# SensorCheck.net
KiCad netlist of a schematic drawn in Altium Designer
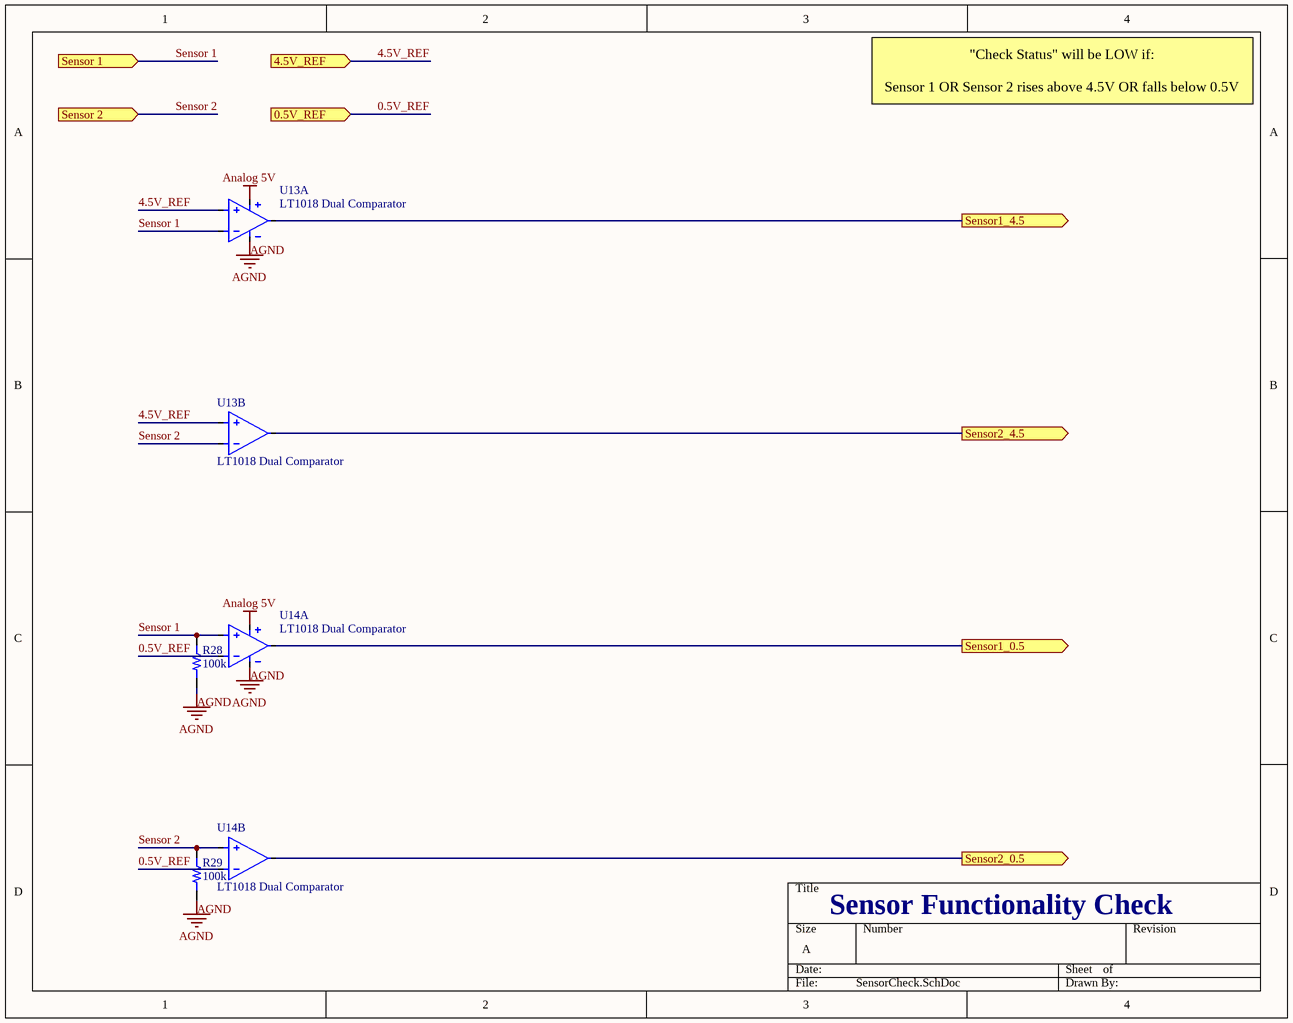
[diagram p0: SensorCheck.SchDoc]

(export (version "E")
  (design (tool "Eeschema 10.0.6"))
  (components
    (comp (ref "R28")
      (value "resistor")
      (footprint "0603")
      (fields (field (name "RESISTANCE") "100k"))
      (libsource (lib "altlib") (part "resistor"))
    )
    (comp (ref "R29")
      (value "resistor")
      (footprint "0603")
      (fields (field (name "RESISTANCE") "100k"))
      (libsource (lib "altlib") (part "resistor"))
    )
    (comp (ref "U13")
      (value "LT1018 Dual Comparator")
      (footprint "SOIC-8")
      (libsource (lib "altlib") (part "LT1018 Dual Comparator"))
    )
    (comp (ref "U14")
      (value "LT1018 Dual Comparator")
      (footprint "SOIC-8")
      (libsource (lib "altlib") (part "LT1018 Dual Comparator"))
    )
  )
  (nets
    (net (code "1") (name "/0.5V_REF") (class "Default")
      (node (ref "U14") (pin "4") (pinfunction "-IN_B_4") (pintype "passive"))
      (node (ref "U14") (pin "8") (pinfunction "-IN_A_8") (pintype "passive"))
    )
    (net (code "2") (name "/4.5V_REF") (class "Default")
      (node (ref "U13") (pin "1") (pinfunction "+IN_A_1") (pintype "passive"))
      (node (ref "U13") (pin "3") (pinfunction "+IN_B_3") (pintype "passive"))
    )
    (net (code "3") (name "/Sensor 1") (class "Default")
      (node (ref "R28") (pin "2") (pinfunction "2_2") (pintype "passive"))
      (node (ref "U13") (pin "8") (pinfunction "-IN_A_8") (pintype "passive"))
      (node (ref "U14") (pin "1") (pinfunction "+IN_A_1") (pintype "passive"))
    )
    (net (code "4") (name "/Sensor 2") (class "Default")
      (node (ref "R29") (pin "2") (pinfunction "2_2") (pintype "passive"))
      (node (ref "U13") (pin "4") (pinfunction "-IN_B_4") (pintype "passive"))
      (node (ref "U14") (pin "3") (pinfunction "+IN_B_3") (pintype "passive"))
    )
    (net (code "5") (name "/Sensor1_0.5") (class "Default")
      (node (ref "U14") (pin "7") (pinfunction "OUT_A_7") (pintype "passive"))
    )
    (net (code "6") (name "/Sensor1_4.5") (class "Default")
      (node (ref "U13") (pin "7") (pinfunction "OUT_A_7") (pintype "passive"))
    )
    (net (code "7") (name "/Sensor2_0.5") (class "Default")
      (node (ref "U14") (pin "5") (pinfunction "OUT_B_5") (pintype "passive"))
    )
    (net (code "8") (name "/Sensor2_4.5") (class "Default")
      (node (ref "U13") (pin "5") (pinfunction "OUT_B_5") (pintype "passive"))
    )
    (net (code "9") (name "AGND") (class "Default")
      (node (ref "R28") (pin "1") (pinfunction "1_1") (pintype "passive"))
      (node (ref "R29") (pin "1") (pinfunction "1_1") (pintype "passive"))
      (node (ref "U13") (pin "2") (pinfunction "V-_2") (pintype "passive"))
      (node (ref "U14") (pin "2") (pinfunction "V-_2") (pintype "passive"))
    )
    (net (code "10") (name "Analog 5V") (class "Default")
      (node (ref "U13") (pin "6") (pinfunction "V+_6") (pintype "passive"))
      (node (ref "U14") (pin "6") (pinfunction "V+_6") (pintype "passive"))
    )
  )
)
